# OPA1622_-_Gain_Stage.net
KiCad netlist of a schematic drawn in EAGLE
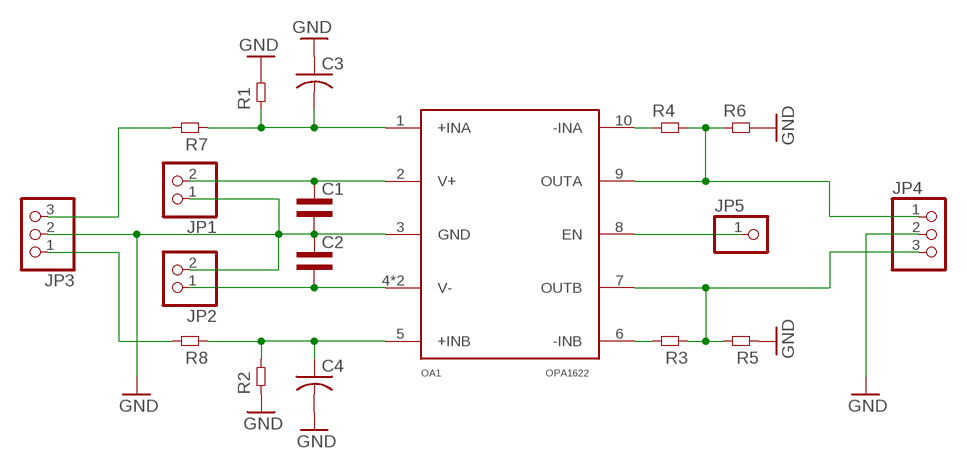
[diagram p0: schematic, sheet 1]

(export (version "E")
  (design (tool "Eeschema 10.0.6"))
  (components
    (comp (ref "C1")
      (value "CAP0603L3")
      (footprint "eagle-import:0603L3")
      (libsource (lib "eagle-import") (part "CAP0603L3"))
    )
    (comp (ref "C2")
      (value "CAP0603L3")
      (footprint "eagle-import:0603L3")
      (libsource (lib "eagle-import") (part "CAP0603L3"))
    )
    (comp (ref "C3")
      (value "C-US025-050X050")
      (footprint "eagle-import:C025-050X050")
      (libsource (lib "eagle-import") (part "C-US025-050X050"))
    )
    (comp (ref "C4")
      (value "C-US025-050X050")
      (footprint "eagle-import:C025-050X050")
      (libsource (lib "eagle-import") (part "C-US025-050X050"))
    )
    (comp (ref "JP1")
      (value "PINHD-1X2")
      (footprint "eagle-import:1X02")
      (libsource (lib "eagle-import") (part "PINHD-1X2"))
    )
    (comp (ref "JP2")
      (value "PINHD-1X2")
      (footprint "eagle-import:1X02")
      (libsource (lib "eagle-import") (part "PINHD-1X2"))
    )
    (comp (ref "JP3")
      (value "PINHD-1X3")
      (footprint "eagle-import:1X03")
      (libsource (lib "eagle-import") (part "PINHD-1X3"))
    )
    (comp (ref "JP4")
      (value "PINHD-1X3")
      (footprint "eagle-import:1X03")
      (libsource (lib "eagle-import") (part "PINHD-1X3"))
    )
    (comp (ref "JP5")
      (value "PINHD-1X1")
      (footprint "eagle-import:1X01")
      (libsource (lib "eagle-import") (part "PINHD-1X1"))
    )
    (comp (ref "OA1")
      (value "OPA1622")
      (footprint "eagle-import:S-PVSON-N10")
      (libsource (lib "eagle-import") (part "OPA1622"))
    )
    (comp (ref "R1")
      (value "RES0603L3")
      (footprint "eagle-import:0603L3")
      (libsource (lib "eagle-import") (part "RES0603L3"))
    )
    (comp (ref "R2")
      (value "RES0603L3")
      (footprint "eagle-import:0603L3")
      (libsource (lib "eagle-import") (part "RES0603L3"))
    )
    (comp (ref "R3")
      (value "RES0603L3")
      (footprint "eagle-import:0603L3")
      (libsource (lib "eagle-import") (part "RES0603L3"))
    )
    (comp (ref "R4")
      (value "RES0603L3")
      (footprint "eagle-import:0603L3")
      (libsource (lib "eagle-import") (part "RES0603L3"))
    )
    (comp (ref "R5")
      (value "RES0603L3")
      (footprint "eagle-import:0603L3")
      (libsource (lib "eagle-import") (part "RES0603L3"))
    )
    (comp (ref "R6")
      (value "RES0603L3")
      (footprint "eagle-import:0603L3")
      (libsource (lib "eagle-import") (part "RES0603L3"))
    )
    (comp (ref "R7")
      (value "RES0603L3")
      (footprint "eagle-import:0603L3")
      (libsource (lib "eagle-import") (part "RES0603L3"))
    )
    (comp (ref "R8")
      (value "RES0603L3")
      (footprint "eagle-import:0603L3")
      (libsource (lib "eagle-import") (part "RES0603L3"))
    )
  )
  (nets
    (net (code "1") (name "GND") (class "Default")
      (node (ref "C1") (pin "P$2") (pinfunction "2_P$2") (pintype "bidirectional"))
      (node (ref "C2") (pin "P$1") (pinfunction "1_P$1") (pintype "bidirectional"))
      (node (ref "C3") (pin "1") (pinfunction "1_1") (pintype "passive"))
      (node (ref "C4") (pin "2") (pinfunction "2_2") (pintype "passive"))
      (node (ref "JP1") (pin "1") (pinfunction "1_1") (pintype "passive"))
      (node (ref "JP2") (pin "2") (pinfunction "2_2") (pintype "passive"))
      (node (ref "JP3") (pin "2") (pinfunction "2_2") (pintype "passive"))
      (node (ref "JP4") (pin "2") (pinfunction "2_2") (pintype "passive"))
      (node (ref "OA1") (pin "3") (pinfunction "GND_3") (pintype "bidirectional"))
      (node (ref "R1") (pin "P$2") (pinfunction "2_P$2") (pintype "bidirectional"))
      (node (ref "R2") (pin "P$1") (pinfunction "1_P$1") (pintype "bidirectional"))
      (node (ref "R5") (pin "P$1") (pinfunction "1_P$1") (pintype "bidirectional"))
      (node (ref "R6") (pin "P$2") (pinfunction "2_P$2") (pintype "bidirectional"))
    )
    (net (code "2") (name "Net-(C1-1)") (class "Default")
      (node (ref "C1") (pin "P$1") (pinfunction "1_P$1") (pintype "bidirectional"))
      (node (ref "JP1") (pin "2") (pinfunction "2_2") (pintype "passive"))
      (node (ref "OA1") (pin "2") (pinfunction "V+_2") (pintype "bidirectional"))
    )
    (net (code "3") (name "Net-(C2-2)") (class "Default")
      (node (ref "C2") (pin "P$2") (pinfunction "2_P$2") (pintype "bidirectional"))
      (node (ref "JP2") (pin "1") (pinfunction "1_1") (pintype "passive"))
      (node (ref "OA1") (pin "4") (pinfunction "V-_4") (pintype "bidirectional"))
      (node (ref "OA1") (pin "TP") (pinfunction "V-_TP") (pintype "bidirectional"))
    )
    (net (code "4") (name "Net-(OA1-+INA)") (class "Default")
      (node (ref "C3") (pin "2") (pinfunction "2_2") (pintype "passive"))
      (node (ref "OA1") (pin "1") (pinfunction "+INA_1") (pintype "bidirectional"))
      (node (ref "R1") (pin "P$1") (pinfunction "1_P$1") (pintype "bidirectional"))
      (node (ref "R7") (pin "P$1") (pinfunction "1_P$1") (pintype "bidirectional"))
    )
    (net (code "5") (name "Net-(OA1-+INB)") (class "Default")
      (node (ref "C4") (pin "1") (pinfunction "1_1") (pintype "passive"))
      (node (ref "OA1") (pin "5") (pinfunction "+INB_5") (pintype "bidirectional"))
      (node (ref "R2") (pin "P$2") (pinfunction "2_P$2") (pintype "bidirectional"))
      (node (ref "R8") (pin "P$1") (pinfunction "1_P$1") (pintype "bidirectional"))
    )
    (net (code "6") (name "Net-(OA1--INA)") (class "Default")
      (node (ref "OA1") (pin "10") (pinfunction "-INA_10") (pintype "bidirectional"))
      (node (ref "R4") (pin "P$1") (pinfunction "1_P$1") (pintype "bidirectional"))
    )
    (net (code "7") (name "Net-(OA1--INB)") (class "Default")
      (node (ref "OA1") (pin "6") (pinfunction "-INB_6") (pintype "bidirectional"))
      (node (ref "R3") (pin "P$2") (pinfunction "2_P$2") (pintype "bidirectional"))
    )
    (net (code "8") (name "Net-(OA1-EN)") (class "Default")
      (node (ref "JP5") (pin "1") (pinfunction "1_1") (pintype "passive"))
      (node (ref "OA1") (pin "8") (pinfunction "EN_8") (pintype "bidirectional"))
    )
    (net (code "9") (name "Net-(OA1-OUTA)") (class "Default")
      (node (ref "JP4") (pin "1") (pinfunction "1_1") (pintype "passive"))
      (node (ref "OA1") (pin "9") (pinfunction "OUTA_9") (pintype "bidirectional"))
      (node (ref "R4") (pin "P$2") (pinfunction "2_P$2") (pintype "bidirectional"))
      (node (ref "R6") (pin "P$1") (pinfunction "1_P$1") (pintype "bidirectional"))
    )
    (net (code "10") (name "Net-(OA1-OUTB)") (class "Default")
      (node (ref "JP4") (pin "3") (pinfunction "3_3") (pintype "passive"))
      (node (ref "OA1") (pin "7") (pinfunction "OUTB_7") (pintype "bidirectional"))
      (node (ref "R3") (pin "P$1") (pinfunction "1_P$1") (pintype "bidirectional"))
      (node (ref "R5") (pin "P$2") (pinfunction "2_P$2") (pintype "bidirectional"))
    )
    (net (code "11") (name "Net-(R7-2)") (class "Default")
      (node (ref "JP3") (pin "3") (pinfunction "3_3") (pintype "passive"))
      (node (ref "R7") (pin "P$2") (pinfunction "2_P$2") (pintype "bidirectional"))
    )
    (net (code "12") (name "Net-(R8-2)") (class "Default")
      (node (ref "JP3") (pin "1") (pinfunction "1_1") (pintype "passive"))
      (node (ref "R8") (pin "P$2") (pinfunction "2_P$2") (pintype "bidirectional"))
    )
  )
)
